# USB-TTL.net
KiCad netlist of a schematic drawn in Altium Designer
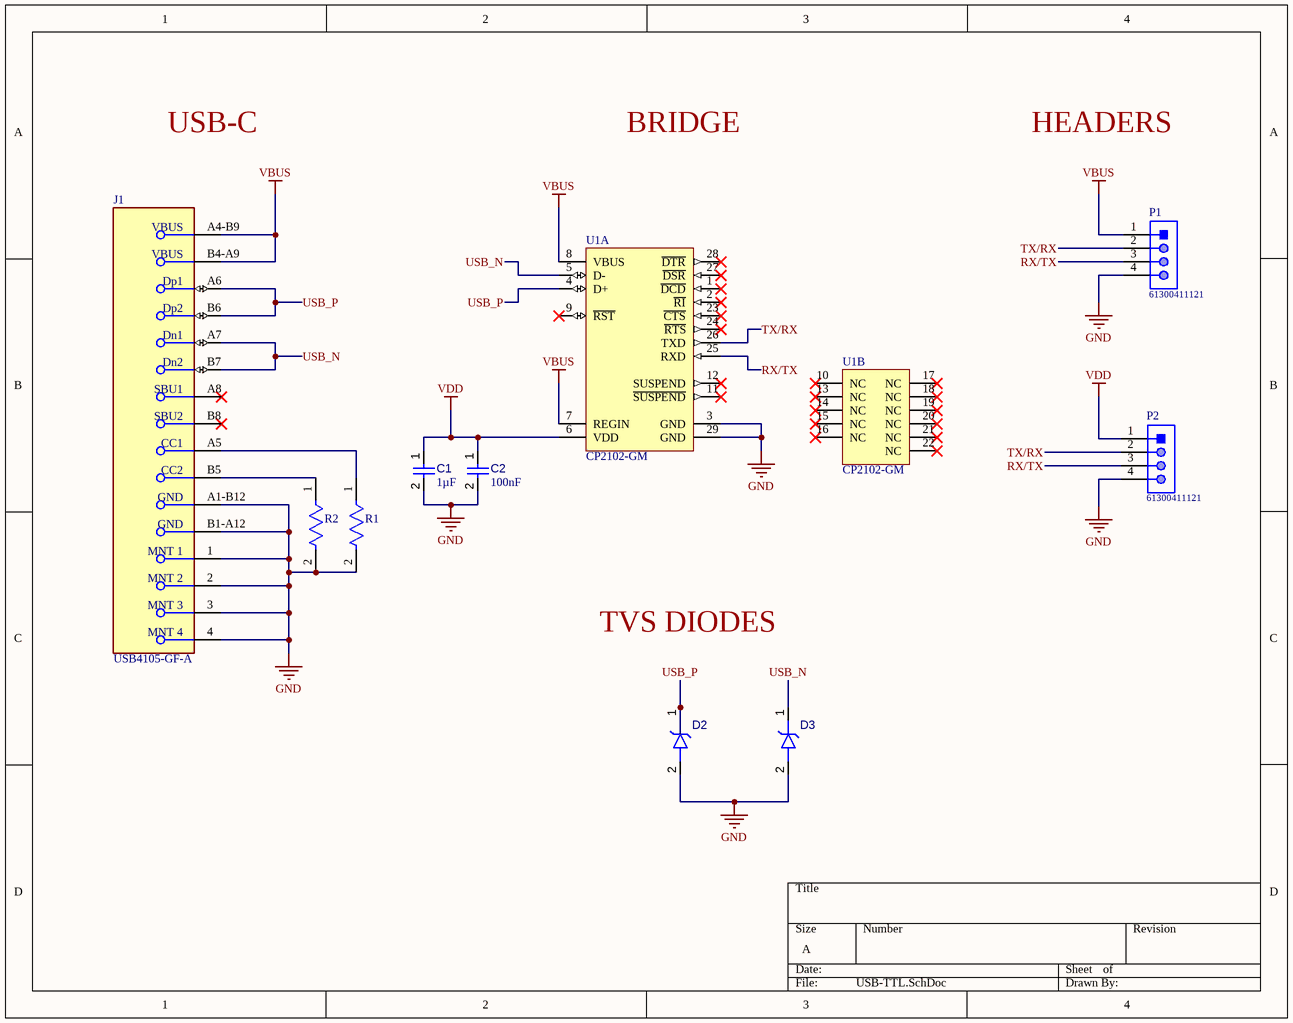
[diagram p0: USB-TTL.SchDoc]

(export (version "E")
  (design (tool "Eeschema 10.0.6"))
  (components
    (comp (ref "C1")
      (value "1µF")
      (footprint "CAPC1608X94X35NL15T15")
      (description "Chip Capacitor, 1 uF, +/- 10%, 16 V, 0603 (1608 Metric)")
      (fields (field (name "TOLERANCE") "10%") (field (name "Comment") "Capacitor 1 uF +/- 10% 16 V 0603"))
      (libsource (lib "University of South Florida") (part "CAP-NP-2"))
    )
    (comp (ref "C2")
      (value "100nF")
      (footprint "CAPC1608X90X40NL10T20")
      (description "Chip Capacitor, 100 nF, +/- 10%, 50 V, 0603 (1608 Metric)")
      (fields (field (name "TOLERANCE") "10%") (field (name "Comment") "Capacitor 100 nF +/-10% 50 V 0603"))
      (libsource (lib "University of South Florida") (part "CAP-NP-2"))
    )
    (comp (ref "D2")
      (value "ESDA25P35-1U1M")
      (footprint "STM-QFN1610")
      (description "TVS DIODE 22V 41V 1610")
      (libsource (lib "University of South Florida") (part "D-TVS-AK-2"))
    )
    (comp (ref "D3")
      (value "ESDA25P35-1U1M")
      (footprint "STM-QFN1610")
      (description "TVS DIODE 22V 41V 1610")
      (libsource (lib "University of South Florida") (part "D-TVS-AK-2"))
    )
    (comp (ref "J1")
      (value "USB4105-GF-A")
      (footprint "FP-USB4105-GF-A-MFG")
      (description "Conn USB 2.0 Type C RCP 24 POS 0.3mm/0.5mm Solder RA SMD 24 Terminal 1 Port T/R")
      (libsource (lib "University of South Florida") (part "e7c17a616881a82b79941196b4bec10"))
    )
    (comp (ref "P1")
      (value "61300411121")
      (footprint "61300411121")
      (description "CONN HEADER 4 POS 2.54")
      (libsource (lib "University of South Florida") (part "WE-CN-1P-M-R4"))
    )
    (comp (ref "P2")
      (value "61300411121")
      (footprint "61300411121")
      (description "CONN HEADER 4 POS 2.54")
      (libsource (lib "University of South Florida") (part "WE-CN-1P-M-R4"))
    )
    (comp (ref "R1")
      (value "ERA-3AEB512V")
      (footprint "FP-ERA3A-MFG")
      (description "Res Thin Film 0603 5.1K Ohm 0.1% 1/10W ±25ppm/°C Molded SMD SMD Punched Carrier T/R")
      (libsource (lib "University of South Florida") (part "8db39607336c341a927600551d01821"))
    )
    (comp (ref "R2")
      (value "ERA-3AEB512V")
      (footprint "FP-ERA3A-MFG")
      (description "Res Thin Film 0603 5.1K Ohm 0.1% 1/10W ±25ppm/°C Molded SMD SMD Punched Carrier T/R")
      (libsource (lib "University of South Florida") (part "8db39607336c341a927600551d01821"))
    )
    (comp (ref "U1")
      (value "CP2102-GM")
      (footprint "SLAB-QFN-28-3125x3125TP_L")
      (description "USB to UART Bridge Controller UART/USB Interface Automotive 28-Pin QFN EP Tube")
      (libsource (lib "") (part "SLAB-CP210X-QFN-28-29_1"))
    )
  )
  (nets
    (net (code "1") (name "/RX{slash}TX") (class "Default")
      (node (ref "P1") (pin "3") (pinfunction "3_3") (pintype "passive"))
      (node (ref "P2") (pin "3") (pinfunction "3_3") (pintype "passive"))
      (node (ref "U1") (pin "25") (pinfunction "RXD_25") (pintype "input"))
    )
    (net (code "2") (name "/TX{slash}RX") (class "Default")
      (node (ref "P1") (pin "2") (pinfunction "2_2") (pintype "passive"))
      (node (ref "P2") (pin "2") (pinfunction "2_2") (pintype "passive"))
      (node (ref "U1") (pin "26") (pinfunction "TXD_26") (pintype "output"))
    )
    (net (code "3") (name "/USB_N") (class "Default")
      (node (ref "D3") (pin "1") (pinfunction "A_1") (pintype "passive"))
      (node (ref "J1") (pin "A7") (pinfunction "Dn1_A7") (pintype "bidirectional"))
      (node (ref "J1") (pin "B7") (pinfunction "Dn2_B7") (pintype "bidirectional"))
      (node (ref "U1") (pin "5") (pinfunction "D-_5") (pintype "bidirectional"))
    )
    (net (code "4") (name "/USB_P") (class "Default")
      (node (ref "D2") (pin "1") (pinfunction "A_1") (pintype "passive"))
      (node (ref "J1") (pin "A6") (pinfunction "Dp1_A6") (pintype "bidirectional"))
      (node (ref "J1") (pin "B6") (pinfunction "Dp2_B6") (pintype "bidirectional"))
      (node (ref "U1") (pin "4") (pinfunction "D+_4") (pintype "bidirectional"))
    )
    (net (code "5") (name "GND") (class "Default")
      (node (ref "C1") (pin "2") (pinfunction "2_2") (pintype "passive"))
      (node (ref "C2") (pin "2") (pinfunction "2_2") (pintype "passive"))
      (node (ref "D2") (pin "2") (pinfunction "A_2") (pintype "passive"))
      (node (ref "D3") (pin "2") (pinfunction "A_2") (pintype "passive"))
      (node (ref "J1") (pin "1") (pinfunction "MNT_1_1") (pintype "power_in"))
      (node (ref "J1") (pin "2") (pinfunction "MNT_2_2") (pintype "power_in"))
      (node (ref "J1") (pin "3") (pinfunction "MNT_3_3") (pintype "power_in"))
      (node (ref "J1") (pin "4") (pinfunction "MNT_4_4") (pintype "power_in"))
      (node (ref "J1") (pin "A1-B12") (pinfunction "GND_A1-B12") (pintype "power_in"))
      (node (ref "J1") (pin "B1-A12") (pinfunction "GND_B1-A12") (pintype "power_in"))
      (node (ref "P1") (pin "4") (pinfunction "4_4") (pintype "passive"))
      (node (ref "P2") (pin "4") (pinfunction "4_4") (pintype "passive"))
      (node (ref "R1") (pin "2") (pinfunction "2_2") (pintype "passive"))
      (node (ref "R2") (pin "2") (pinfunction "2_2") (pintype "passive"))
      (node (ref "U1") (pin "29") (pinfunction "GND_29") (pintype "power_in"))
      (node (ref "U1") (pin "3") (pinfunction "GND_3") (pintype "power_in"))
    )
    (net (code "6") (name "Net-(J1-CC1)") (class "Default")
      (node (ref "J1") (pin "A5") (pinfunction "CC1_A5") (pintype "passive"))
      (node (ref "R1") (pin "1") (pinfunction "1_1") (pintype "passive"))
    )
    (net (code "7") (name "Net-(J1-CC2)") (class "Default")
      (node (ref "J1") (pin "B5") (pinfunction "CC2_B5") (pintype "passive"))
      (node (ref "R2") (pin "1") (pinfunction "1_1") (pintype "passive"))
    )
    (net (code "8") (name "VBUS") (class "Default")
      (node (ref "J1") (pin "A4-B9") (pinfunction "VBUS_A4-B9") (pintype "power_in"))
      (node (ref "J1") (pin "B4-A9") (pinfunction "VBUS_B4-A9") (pintype "power_in"))
      (node (ref "P1") (pin "1") (pinfunction "1_1") (pintype "passive"))
      (node (ref "U1") (pin "7") (pinfunction "REGIN_7") (pintype "power_in"))
      (node (ref "U1") (pin "8") (pinfunction "VBUS_8") (pintype "power_in"))
    )
    (net (code "9") (name "VDD") (class "Default")
      (node (ref "C1") (pin "1") (pinfunction "1_1") (pintype "passive"))
      (node (ref "C2") (pin "1") (pinfunction "1_1") (pintype "passive"))
      (node (ref "P2") (pin "1") (pinfunction "1_1") (pintype "passive"))
      (node (ref "U1") (pin "6") (pinfunction "VDD_6") (pintype "power_in"))
    )
    (net (code "10") (name "unconnected-(J1-SBU1-PadA8)") (class "Default")
      (node (ref "J1") (pin "A8") (pinfunction "SBU1_A8") (pintype "passive+no_connect"))
    )
    (net (code "11") (name "unconnected-(J1-SBU2-PadB8)") (class "Default")
      (node (ref "J1") (pin "B8") (pinfunction "SBU2_B8") (pintype "passive+no_connect"))
    )
    (net (code "12") (name "unconnected-(U1A-SUSPEND-Pad12)") (class "Default")
      (node (ref "U1") (pin "12") (pinfunction "SUSPEND_12") (pintype "output+no_connect"))
    )
    (net (code "13") (name "unconnected-(U1A-~{CTS}-Pad23)") (class "Default")
      (node (ref "U1") (pin "23") (pinfunction "~{CTS}_23") (pintype "input+no_connect"))
    )
    (net (code "14") (name "unconnected-(U1A-~{DCD}-Pad1)") (class "Default")
      (node (ref "U1") (pin "1") (pinfunction "~{DCD}_1") (pintype "input+no_connect"))
    )
    (net (code "15") (name "unconnected-(U1A-~{DSR}-Pad27)") (class "Default")
      (node (ref "U1") (pin "27") (pinfunction "~{DSR}_27") (pintype "input+no_connect"))
    )
    (net (code "16") (name "unconnected-(U1A-~{DTR}-Pad28)") (class "Default")
      (node (ref "U1") (pin "28") (pinfunction "~{DTR}_28") (pintype "output+no_connect"))
    )
    (net (code "17") (name "unconnected-(U1A-~{RI}-Pad2)") (class "Default")
      (node (ref "U1") (pin "2") (pinfunction "~{RI}_2") (pintype "input+no_connect"))
    )
    (net (code "18") (name "unconnected-(U1A-~{RST}-Pad9)") (class "Default")
      (node (ref "U1") (pin "9") (pinfunction "~{RST}_9") (pintype "bidirectional+no_connect"))
    )
    (net (code "19") (name "unconnected-(U1A-~{RTS}-Pad24)") (class "Default")
      (node (ref "U1") (pin "24") (pinfunction "~{RTS}_24") (pintype "output+no_connect"))
    )
    (net (code "20") (name "unconnected-(U1A-~{SUSPEND}-Pad11)") (class "Default")
      (node (ref "U1") (pin "11") (pinfunction "~{SUSPEND}_11") (pintype "output+no_connect"))
    )
    (net (code "21") (name "unconnected-(U1B-NC-Pad10)") (class "Default")
      (node (ref "U1") (pin "10") (pinfunction "NC_10") (pintype "passive+no_connect"))
    )
    (net (code "22") (name "unconnected-(U1B-NC-Pad13)") (class "Default")
      (node (ref "U1") (pin "13") (pinfunction "NC_13") (pintype "passive+no_connect"))
    )
    (net (code "23") (name "unconnected-(U1B-NC-Pad14)") (class "Default")
      (node (ref "U1") (pin "14") (pinfunction "NC_14") (pintype "passive+no_connect"))
    )
    (net (code "24") (name "unconnected-(U1B-NC-Pad15)") (class "Default")
      (node (ref "U1") (pin "15") (pinfunction "NC_15") (pintype "passive+no_connect"))
    )
    (net (code "25") (name "unconnected-(U1B-NC-Pad16)") (class "Default")
      (node (ref "U1") (pin "16") (pinfunction "NC_16") (pintype "passive+no_connect"))
    )
    (net (code "26") (name "unconnected-(U1B-NC-Pad17)") (class "Default")
      (node (ref "U1") (pin "17") (pinfunction "NC_17") (pintype "passive+no_connect"))
    )
    (net (code "27") (name "unconnected-(U1B-NC-Pad18)") (class "Default")
      (node (ref "U1") (pin "18") (pinfunction "NC_18") (pintype "passive+no_connect"))
    )
    (net (code "28") (name "unconnected-(U1B-NC-Pad19)") (class "Default")
      (node (ref "U1") (pin "19") (pinfunction "NC_19") (pintype "passive+no_connect"))
    )
    (net (code "29") (name "unconnected-(U1B-NC-Pad20)") (class "Default")
      (node (ref "U1") (pin "20") (pinfunction "NC_20") (pintype "passive+no_connect"))
    )
    (net (code "30") (name "unconnected-(U1B-NC-Pad21)") (class "Default")
      (node (ref "U1") (pin "21") (pinfunction "NC_21") (pintype "passive+no_connect"))
    )
    (net (code "31") (name "unconnected-(U1B-NC-Pad22)") (class "Default")
      (node (ref "U1") (pin "22") (pinfunction "NC_22") (pintype "passive+no_connect"))
    )
  )
)
